# garden-bot.net
KiCad netlist of a schematic drawn in EAGLE
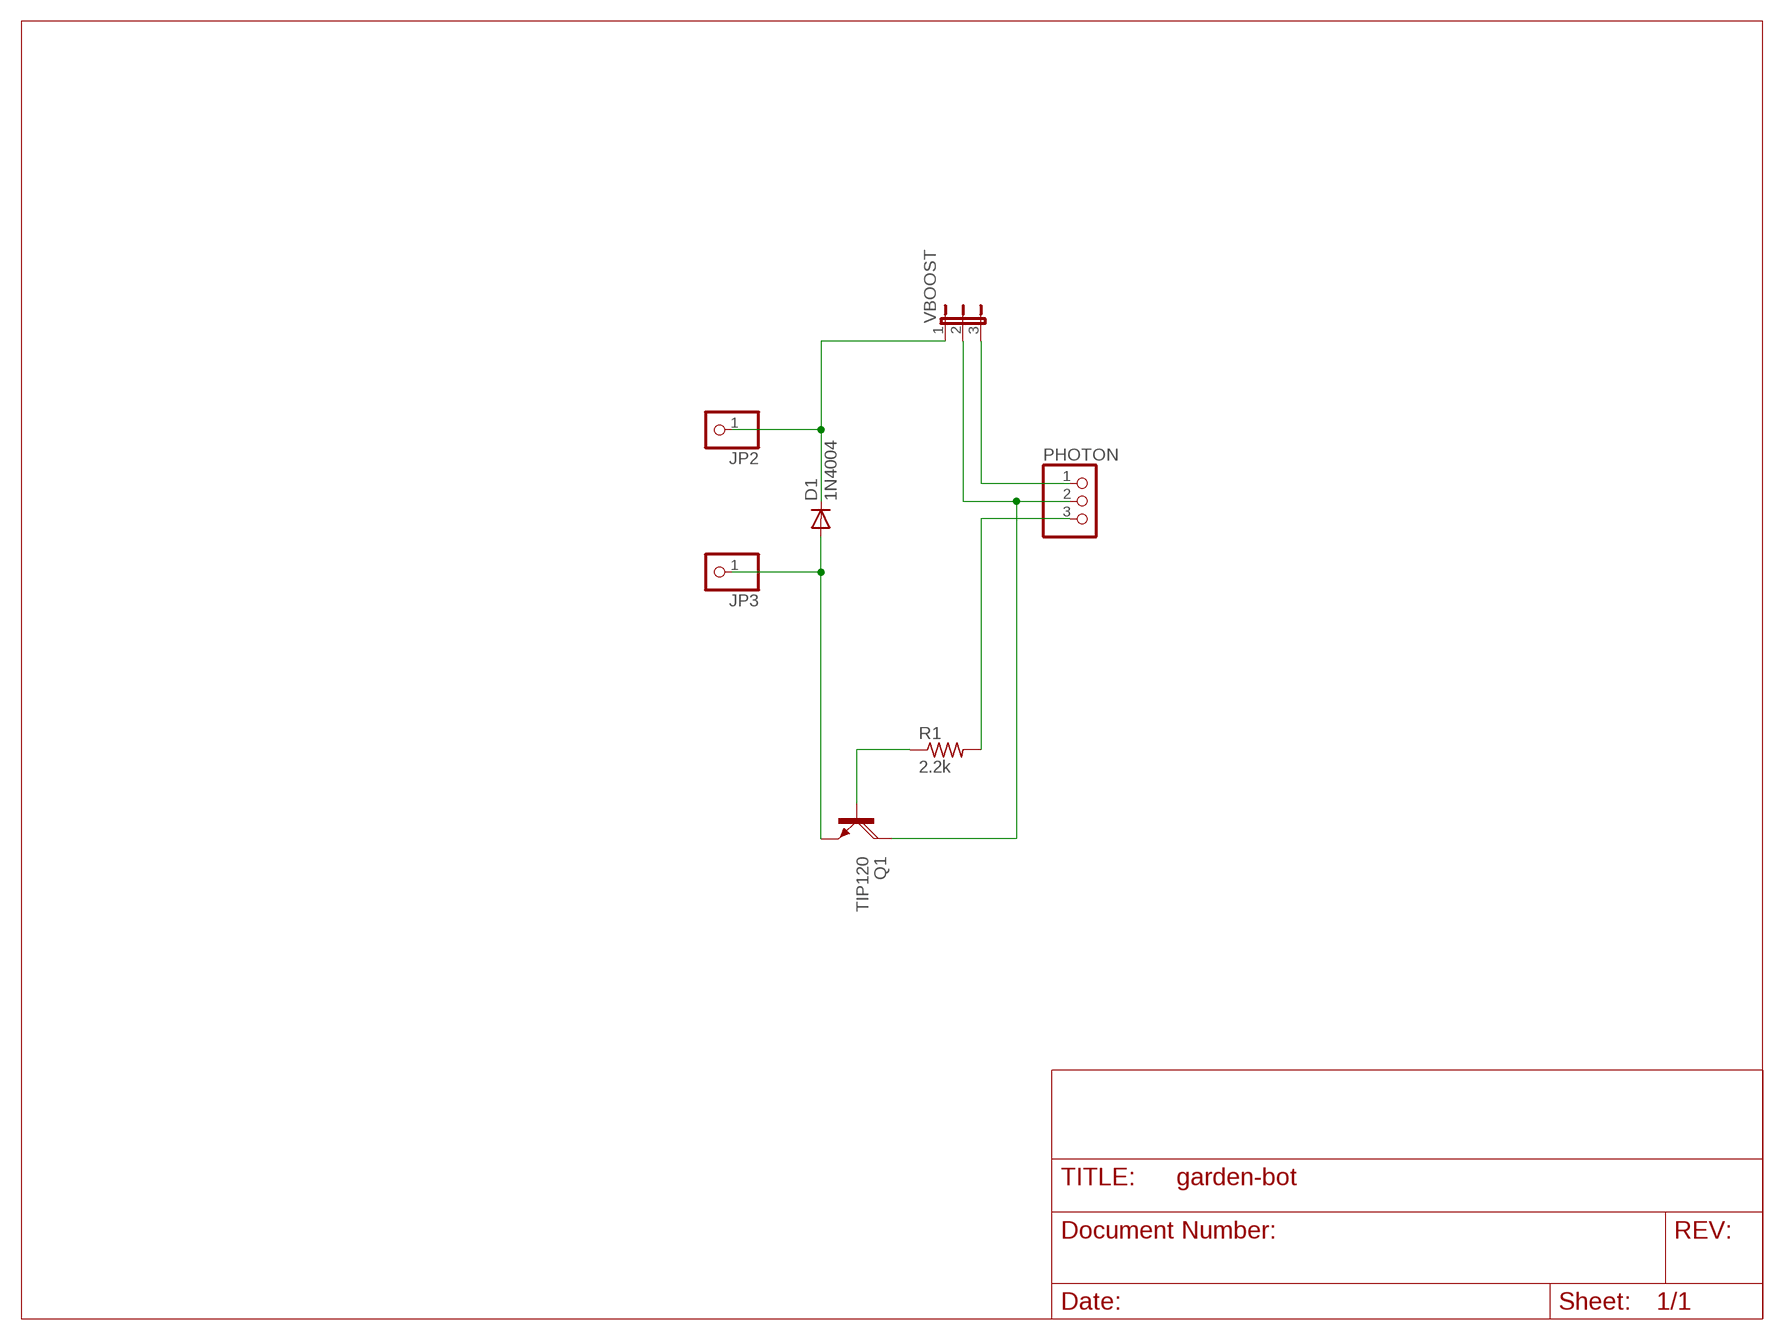
[diagram p0: schematic, sheet 1]

(export (version "E")
  (design (tool "Eeschema 10.0.6"))
  (components
    (comp (ref "D1")
      (value "1N4004")
      (footprint "eagle-import:DO41-10")
      (libsource (lib "eagle-import") (part "1N4004"))
    )
    (comp (ref "JP2")
      (value "PINHD-1X1")
      (footprint "eagle-import:1X01")
      (libsource (lib "eagle-import") (part "PINHD-1X1"))
    )
    (comp (ref "JP3")
      (value "PINHD-1X1")
      (footprint "eagle-import:1X01")
      (libsource (lib "eagle-import") (part "PINHD-1X1"))
    )
    (comp (ref "PHOTON")
      (value "PINHD-1X3")
      (footprint "eagle-import:1X03")
      (libsource (lib "eagle-import") (part "PINHD-1X3"))
    )
    (comp (ref "Q1")
      (value "TIP120")
      (footprint "eagle-import:TO220AH")
      (libsource (lib "eagle-import") (part "TIP120"))
    )
    (comp (ref "R1")
      (value "2.2k")
      (footprint "eagle-import:0207_10")
      (libsource (lib "eagle-import") (part "R-US_0207/10"))
    )
    (comp (ref "VBOOST")
      (value "JP2E")
      (footprint "eagle-import:JP2")
      (libsource (lib "eagle-import") (part "JP2E"))
    )
  )
  (nets
    (net (code "1") (name "Net-(D1-PadA)") (class "Default")
      (node (ref "D1") (pin "A") (pinfunction "A_A") (pintype "passive"))
      (node (ref "JP3") (pin "1") (pinfunction "1_1") (pintype "passive"))
      (node (ref "Q1") (pin "E") (pinfunction "E_E") (pintype "passive"))
    )
    (net (code "2") (name "Net-(D1-PadC)") (class "Default")
      (node (ref "D1") (pin "C") (pinfunction "C_C") (pintype "passive"))
      (node (ref "JP2") (pin "1") (pinfunction "1_1") (pintype "passive"))
      (node (ref "VBOOST") (pin "1") (pinfunction "1_1") (pintype "passive"))
    )
    (net (code "3") (name "Net-(PHOTON-Pad1)") (class "Default")
      (node (ref "PHOTON") (pin "1") (pinfunction "1_1") (pintype "passive"))
      (node (ref "VBOOST") (pin "3") (pinfunction "3_3") (pintype "passive"))
    )
    (net (code "4") (name "Net-(PHOTON-Pad2)") (class "Default")
      (node (ref "PHOTON") (pin "2") (pinfunction "2_2") (pintype "passive"))
      (node (ref "Q1") (pin "C") (pinfunction "C_C") (pintype "passive"))
      (node (ref "VBOOST") (pin "2") (pinfunction "2_2") (pintype "passive"))
    )
    (net (code "5") (name "Net-(PHOTON-Pad3)") (class "Default")
      (node (ref "PHOTON") (pin "3") (pinfunction "3_3") (pintype "passive"))
      (node (ref "R1") (pin "2") (pinfunction "2_2") (pintype "passive"))
    )
    (net (code "6") (name "Net-(Q1-PadB)") (class "Default")
      (node (ref "Q1") (pin "B") (pinfunction "B_B") (pintype "passive"))
      (node (ref "R1") (pin "1") (pinfunction "1_1") (pintype "passive"))
    )
  )
)
